# EasyEDA_ChisFlash_V1_0_Prometheus.net
KiCad netlist of a schematic drawn in EasyEDA Pro
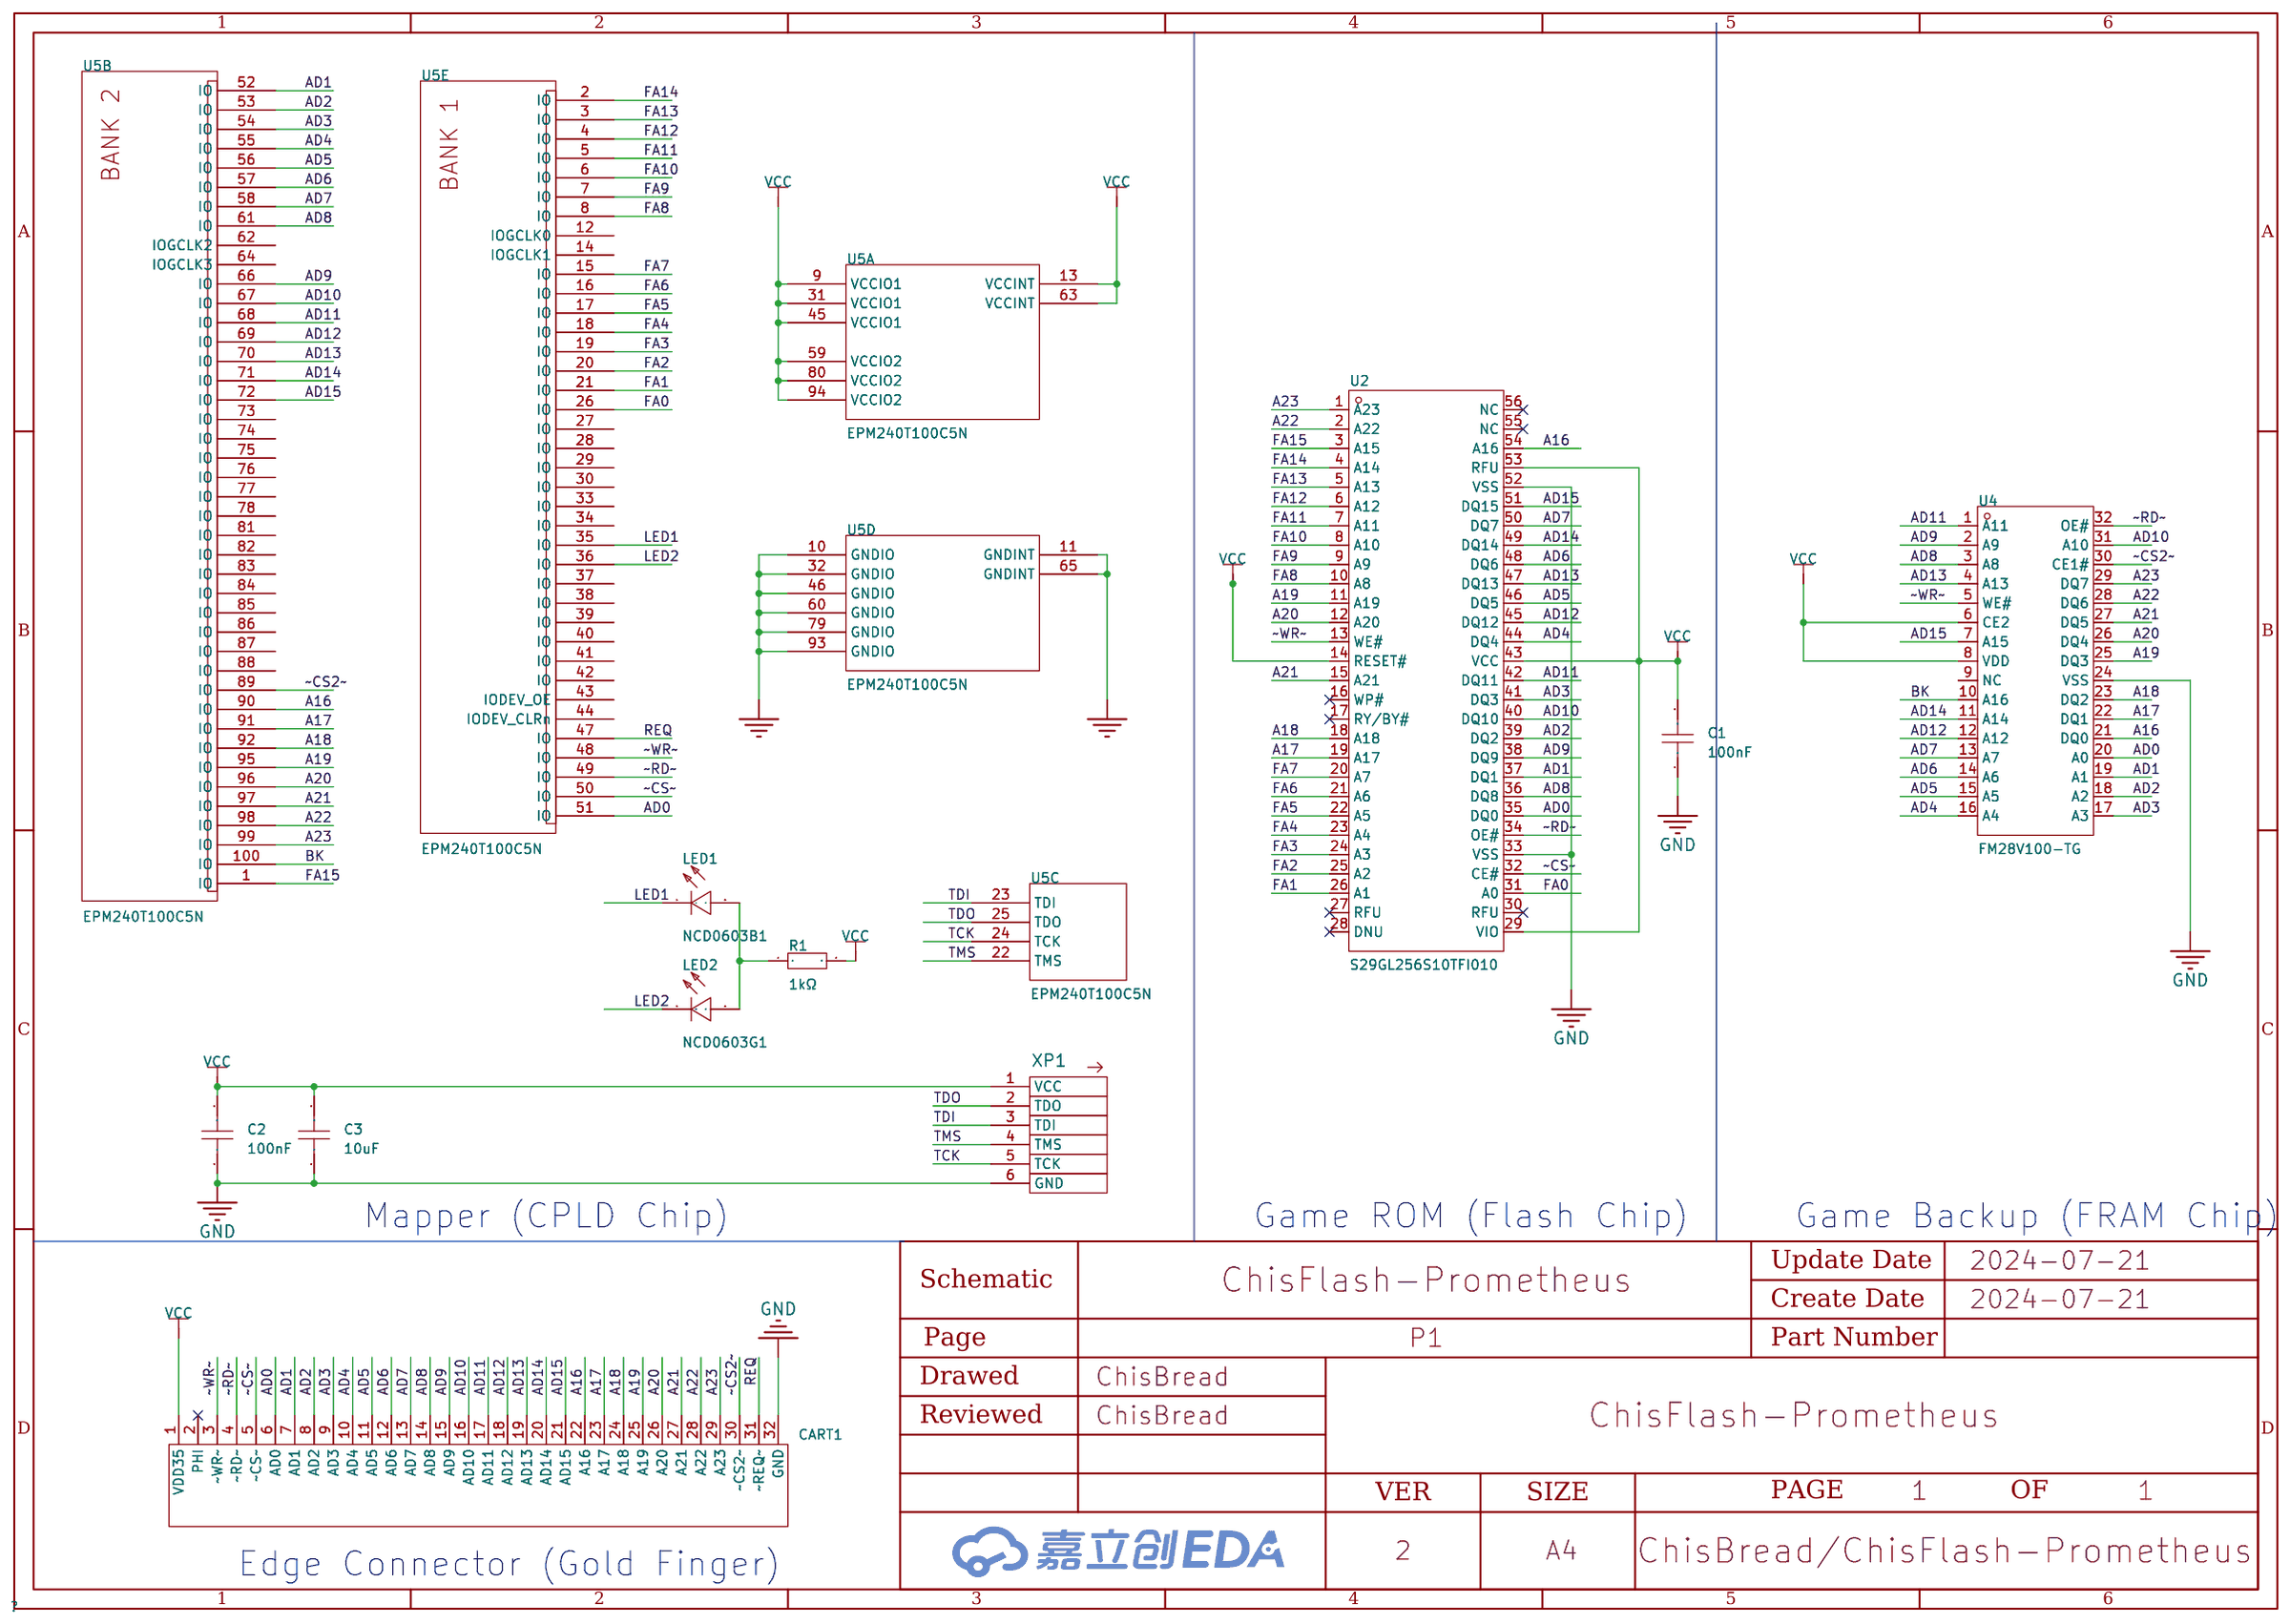
[diagram p0: schematic sheet]

(export (version "E")
  (design (tool "Eeschema 10.0.6"))
  (components
    (comp (ref "C1")
      (value "100nF")
      (footprint "easyedapro:C0603")
      (libsource (lib "easyedapro") (part "CapAcitance"))
    )
    (comp (ref "C2")
      (value "100nF")
      (footprint "easyedapro:C0603")
      (libsource (lib "easyedapro") (part "CapAcitance"))
    )
    (comp (ref "C3")
      (value "10uF")
      (footprint "easyedapro:C0603")
      (description "容值:10uF;精度:±20%;额定电压:25V;材质(温度系数):X5R;")
      (fields
        (field (name "Manufacturer Part") "CL10A106MA8NRNC")
        (field (name "Manufacturer") "SAMSUNG(三星)")
      )
      (libsource (lib "easyedapro") (part "CL10A106MA8NRNC"))
    )
    (comp (ref "CART1")
      (value "~")
      (footprint "easyedapro:GBACartridge")
      (description "GBA Cartridge")
      (libsource (lib "easyedapro") (part "GBACartridge"))
    )
    (comp (ref "LED1")
      (value "NCD0603B1")
      (footprint "easyedapro:LED0603-RD")
      (fields (field (name "Manufacturer") "国星光电"))
      (libsource (lib "easyedapro") (part "FC-DA1608BK-470H10"))
    )
    (comp (ref "LED2")
      (value "NCD0603G1")
      (footprint "easyedapro:LED0603-RD")
      (fields (field (name "Manufacturer") "国星光电"))
      (libsource (lib "easyedapro") (part "FC-D1608UGK-520D10"))
    )
    (comp (ref "R1")
      (value "1kΩ")
      (footprint "easyedapro:R0603")
      (description "电阻类型:厚膜电阻;阻值:1kΩ;精度:±1%;功率:100mW;最大工作电压:75V;温度系数:±100ppm/°C;")
      (fields
        (field (name "Manufacturer Part") "0603WAF1001T5E")
        (field (name "Manufacturer") "UNI-ROYAL(厚声)")
      )
      (libsource (lib "easyedapro") (part "0603WAF1001T5E"))
    )
    (comp (ref "U2")
      (value "S29GL256S10TFI010")
      (footprint "easyedapro:TSOP-56_L18.4-W14.0-P0.50-LS20.0-TL")
      (fields (field (name "Manufacturer") "SPANSION(飞索)"))
      (libsource (lib "easyedapro") (part "S29GL256S10TFI010"))
    )
    (comp (ref "U4")
      (value "FM28V100-TG")
      (fields (field (name "Manufacturer") "CYPRESS(赛普拉斯)"))
      (libsource (lib "easyedapro") (part "FM28V100-TG_C2959453"))
    )
    (comp (ref "U5")
      (value "EPM240T100C5N")
      (footprint "easyedapro:TQFP-100_L14.0-W14.0-P0.50-LS16.0-BL")
      (description "类型:其它PLD;逻辑门数量:-;逻辑单元数:-;逻辑阵列块数:240;")
      (fields (field (name "Manufacturer") "Intel/Altera"))
      (libsource (lib "easyedapro") (part "EPM240T100C5N"))
    )
    (comp (ref "XP1")
      (value "JTAG")
      (footprint "easyedapro:HDR-TH_6P-P1.27-V-M-1")
      (libsource (lib "easyedapro") (part "jtag"))
    )
  )
  (nets
    (net (code "1") (name "/A16") (class "Default")
      (node (ref "CART1") (pin "22") (pinfunction "A16_22") (pintype "input"))
      (node (ref "U2") (pin "54") (pinfunction "A16_54") (pintype "input"))
      (node (ref "U4") (pin "21") (pinfunction "DQ0_21") (pintype "unspecified"))
      (node (ref "U5") (pin "90") (pinfunction "IO_90") (pintype "bidirectional"))
    )
    (net (code "2") (name "/A17") (class "Default")
      (node (ref "CART1") (pin "23") (pinfunction "A17_23") (pintype "input"))
      (node (ref "U2") (pin "19") (pinfunction "A17_19") (pintype "input"))
      (node (ref "U4") (pin "22") (pinfunction "DQ1_22") (pintype "unspecified"))
      (node (ref "U5") (pin "91") (pinfunction "IO_91") (pintype "bidirectional"))
    )
    (net (code "3") (name "/A18") (class "Default")
      (node (ref "CART1") (pin "24") (pinfunction "A18_24") (pintype "input"))
      (node (ref "U2") (pin "18") (pinfunction "A18_18") (pintype "input"))
      (node (ref "U4") (pin "23") (pinfunction "DQ2_23") (pintype "unspecified"))
      (node (ref "U5") (pin "92") (pinfunction "IO_92") (pintype "bidirectional"))
    )
    (net (code "4") (name "/A19") (class "Default")
      (node (ref "CART1") (pin "25") (pinfunction "A19_25") (pintype "input"))
      (node (ref "U2") (pin "11") (pinfunction "A19_11") (pintype "input"))
      (node (ref "U4") (pin "25") (pinfunction "DQ3_25") (pintype "unspecified"))
      (node (ref "U5") (pin "95") (pinfunction "IO_95") (pintype "bidirectional"))
    )
    (net (code "5") (name "/A20") (class "Default")
      (node (ref "CART1") (pin "26") (pinfunction "A20_26") (pintype "input"))
      (node (ref "U2") (pin "12") (pinfunction "A20_12") (pintype "input"))
      (node (ref "U4") (pin "26") (pinfunction "DQ4_26") (pintype "unspecified"))
      (node (ref "U5") (pin "96") (pinfunction "IO_96") (pintype "bidirectional"))
    )
    (net (code "6") (name "/A21") (class "Default")
      (node (ref "CART1") (pin "27") (pinfunction "A21_27") (pintype "input"))
      (node (ref "U2") (pin "15") (pinfunction "A21_15") (pintype "input"))
      (node (ref "U4") (pin "27") (pinfunction "DQ5_27") (pintype "unspecified"))
      (node (ref "U5") (pin "97") (pinfunction "IO_97") (pintype "bidirectional"))
    )
    (net (code "7") (name "/A22") (class "Default")
      (node (ref "CART1") (pin "28") (pinfunction "A22_28") (pintype "input"))
      (node (ref "U2") (pin "2") (pinfunction "A22_2") (pintype "input"))
      (node (ref "U4") (pin "28") (pinfunction "DQ6_28") (pintype "unspecified"))
      (node (ref "U5") (pin "98") (pinfunction "IO_98") (pintype "bidirectional"))
    )
    (net (code "8") (name "/A23") (class "Default")
      (node (ref "CART1") (pin "29") (pinfunction "A23_29") (pintype "input"))
      (node (ref "U2") (pin "1") (pinfunction "A23_1") (pintype "input"))
      (node (ref "U4") (pin "29") (pinfunction "DQ7_29") (pintype "unspecified"))
      (node (ref "U5") (pin "99") (pinfunction "IO_99") (pintype "bidirectional"))
    )
    (net (code "9") (name "/AD0") (class "Default")
      (node (ref "CART1") (pin "6") (pinfunction "AD0_6") (pintype "input"))
      (node (ref "U2") (pin "35") (pinfunction "DQ0_35") (pintype "input"))
      (node (ref "U4") (pin "20") (pinfunction "A0_20") (pintype "unspecified"))
      (node (ref "U5") (pin "51") (pinfunction "IO_51") (pintype "bidirectional"))
    )
    (net (code "10") (name "/AD1") (class "Default")
      (node (ref "CART1") (pin "7") (pinfunction "AD1_7") (pintype "input"))
      (node (ref "U2") (pin "37") (pinfunction "DQ1_37") (pintype "input"))
      (node (ref "U4") (pin "19") (pinfunction "A1_19") (pintype "unspecified"))
      (node (ref "U5") (pin "52") (pinfunction "IO_52") (pintype "bidirectional"))
    )
    (net (code "11") (name "/AD2") (class "Default")
      (node (ref "CART1") (pin "8") (pinfunction "AD2_8") (pintype "input"))
      (node (ref "U2") (pin "39") (pinfunction "DQ2_39") (pintype "input"))
      (node (ref "U4") (pin "18") (pinfunction "A2_18") (pintype "unspecified"))
      (node (ref "U5") (pin "53") (pinfunction "IO_53") (pintype "bidirectional"))
    )
    (net (code "12") (name "/AD3") (class "Default")
      (node (ref "CART1") (pin "9") (pinfunction "AD3_9") (pintype "input"))
      (node (ref "U2") (pin "41") (pinfunction "DQ3_41") (pintype "input"))
      (node (ref "U4") (pin "17") (pinfunction "A3_17") (pintype "unspecified"))
      (node (ref "U5") (pin "54") (pinfunction "IO_54") (pintype "bidirectional"))
    )
    (net (code "13") (name "/AD4") (class "Default")
      (node (ref "CART1") (pin "10") (pinfunction "AD4_10") (pintype "input"))
      (node (ref "U2") (pin "44") (pinfunction "DQ4_44") (pintype "input"))
      (node (ref "U4") (pin "16") (pinfunction "A4_16") (pintype "unspecified"))
      (node (ref "U5") (pin "55") (pinfunction "IO_55") (pintype "bidirectional"))
    )
    (net (code "14") (name "/AD5") (class "Default")
      (node (ref "CART1") (pin "11") (pinfunction "AD5_11") (pintype "input"))
      (node (ref "U2") (pin "46") (pinfunction "DQ5_46") (pintype "input"))
      (node (ref "U4") (pin "15") (pinfunction "A5_15") (pintype "unspecified"))
      (node (ref "U5") (pin "56") (pinfunction "IO_56") (pintype "bidirectional"))
    )
    (net (code "15") (name "/AD6") (class "Default")
      (node (ref "CART1") (pin "12") (pinfunction "AD6_12") (pintype "input"))
      (node (ref "U2") (pin "48") (pinfunction "DQ6_48") (pintype "input"))
      (node (ref "U4") (pin "14") (pinfunction "A6_14") (pintype "unspecified"))
      (node (ref "U5") (pin "57") (pinfunction "IO_57") (pintype "bidirectional"))
    )
    (net (code "16") (name "/AD7") (class "Default")
      (node (ref "CART1") (pin "13") (pinfunction "AD7_13") (pintype "input"))
      (node (ref "U2") (pin "50") (pinfunction "DQ7_50") (pintype "input"))
      (node (ref "U4") (pin "13") (pinfunction "A7_13") (pintype "unspecified"))
      (node (ref "U5") (pin "58") (pinfunction "IO_58") (pintype "bidirectional"))
    )
    (net (code "17") (name "/AD8") (class "Default")
      (node (ref "CART1") (pin "14") (pinfunction "AD8_14") (pintype "input"))
      (node (ref "U2") (pin "36") (pinfunction "DQ8_36") (pintype "input"))
      (node (ref "U4") (pin "3") (pinfunction "A8_3") (pintype "unspecified"))
      (node (ref "U5") (pin "61") (pinfunction "IO_61") (pintype "bidirectional"))
    )
    (net (code "18") (name "/AD9") (class "Default")
      (node (ref "CART1") (pin "15") (pinfunction "AD9_15") (pintype "input"))
      (node (ref "U2") (pin "38") (pinfunction "DQ9_38") (pintype "input"))
      (node (ref "U4") (pin "2") (pinfunction "A9_2") (pintype "unspecified"))
      (node (ref "U5") (pin "66") (pinfunction "IO_66") (pintype "bidirectional"))
    )
    (net (code "19") (name "/AD10") (class "Default")
      (node (ref "CART1") (pin "16") (pinfunction "AD10_16") (pintype "input"))
      (node (ref "U2") (pin "40") (pinfunction "DQ10_40") (pintype "input"))
      (node (ref "U4") (pin "31") (pinfunction "A10_31") (pintype "unspecified"))
      (node (ref "U5") (pin "67") (pinfunction "IO_67") (pintype "bidirectional"))
    )
    (net (code "20") (name "/AD11") (class "Default")
      (node (ref "CART1") (pin "17") (pinfunction "AD11_17") (pintype "input"))
      (node (ref "U2") (pin "42") (pinfunction "DQ11_42") (pintype "input"))
      (node (ref "U4") (pin "1") (pinfunction "A11_1") (pintype "unspecified"))
      (node (ref "U5") (pin "68") (pinfunction "IO_68") (pintype "bidirectional"))
    )
    (net (code "21") (name "/AD12") (class "Default")
      (node (ref "CART1") (pin "18") (pinfunction "AD12_18") (pintype "input"))
      (node (ref "U2") (pin "45") (pinfunction "DQ12_45") (pintype "input"))
      (node (ref "U4") (pin "12") (pinfunction "A12_12") (pintype "unspecified"))
      (node (ref "U5") (pin "69") (pinfunction "IO_69") (pintype "bidirectional"))
    )
    (net (code "22") (name "/AD13") (class "Default")
      (node (ref "CART1") (pin "19") (pinfunction "AD13_19") (pintype "input"))
      (node (ref "U2") (pin "47") (pinfunction "DQ13_47") (pintype "input"))
      (node (ref "U4") (pin "4") (pinfunction "A13_4") (pintype "unspecified"))
      (node (ref "U5") (pin "70") (pinfunction "IO_70") (pintype "bidirectional"))
    )
    (net (code "23") (name "/AD14") (class "Default")
      (node (ref "CART1") (pin "20") (pinfunction "AD14_20") (pintype "input"))
      (node (ref "U2") (pin "49") (pinfunction "DQ14_49") (pintype "input"))
      (node (ref "U4") (pin "11") (pinfunction "A14_11") (pintype "unspecified"))
      (node (ref "U5") (pin "71") (pinfunction "IO_71") (pintype "bidirectional"))
    )
    (net (code "24") (name "/AD15") (class "Default")
      (node (ref "CART1") (pin "21") (pinfunction "AD15_21") (pintype "input"))
      (node (ref "U2") (pin "51") (pinfunction "DQ15_51") (pintype "input"))
      (node (ref "U4") (pin "7") (pinfunction "A15_7") (pintype "unspecified"))
      (node (ref "U5") (pin "72") (pinfunction "IO_72") (pintype "bidirectional"))
    )
    (net (code "25") (name "/BK") (class "Default")
      (node (ref "U4") (pin "10") (pinfunction "A16_10") (pintype "unspecified"))
      (node (ref "U5") (pin "100") (pinfunction "IO_100") (pintype "bidirectional"))
    )
    (net (code "26") (name "/FA0") (class "Default")
      (node (ref "U2") (pin "31") (pinfunction "A0_31") (pintype "input"))
      (node (ref "U5") (pin "26") (pinfunction "IO_26") (pintype "bidirectional"))
    )
    (net (code "27") (name "/FA1") (class "Default")
      (node (ref "U2") (pin "26") (pinfunction "A1_26") (pintype "input"))
      (node (ref "U5") (pin "21") (pinfunction "IO_21") (pintype "bidirectional"))
    )
    (net (code "28") (name "/FA2") (class "Default")
      (node (ref "U2") (pin "25") (pinfunction "A2_25") (pintype "input"))
      (node (ref "U5") (pin "20") (pinfunction "IO_20") (pintype "bidirectional"))
    )
    (net (code "29") (name "/FA3") (class "Default")
      (node (ref "U2") (pin "24") (pinfunction "A3_24") (pintype "input"))
      (node (ref "U5") (pin "19") (pinfunction "IO_19") (pintype "bidirectional"))
    )
    (net (code "30") (name "/FA4") (class "Default")
      (node (ref "U2") (pin "23") (pinfunction "A4_23") (pintype "input"))
      (node (ref "U5") (pin "18") (pinfunction "IO_18") (pintype "bidirectional"))
    )
    (net (code "31") (name "/FA5") (class "Default")
      (node (ref "U2") (pin "22") (pinfunction "A5_22") (pintype "input"))
      (node (ref "U5") (pin "17") (pinfunction "IO_17") (pintype "bidirectional"))
    )
    (net (code "32") (name "/FA6") (class "Default")
      (node (ref "U2") (pin "21") (pinfunction "A6_21") (pintype "input"))
      (node (ref "U5") (pin "16") (pinfunction "IO_16") (pintype "bidirectional"))
    )
    (net (code "33") (name "/FA7") (class "Default")
      (node (ref "U2") (pin "20") (pinfunction "A7_20") (pintype "input"))
      (node (ref "U5") (pin "15") (pinfunction "IO_15") (pintype "bidirectional"))
    )
    (net (code "34") (name "/FA8") (class "Default")
      (node (ref "U2") (pin "10") (pinfunction "A8_10") (pintype "input"))
      (node (ref "U5") (pin "8") (pinfunction "IO_8") (pintype "bidirectional"))
    )
    (net (code "35") (name "/FA9") (class "Default")
      (node (ref "U2") (pin "9") (pinfunction "A9_9") (pintype "input"))
      (node (ref "U5") (pin "7") (pinfunction "IO_7") (pintype "bidirectional"))
    )
    (net (code "36") (name "/FA10") (class "Default")
      (node (ref "U2") (pin "8") (pinfunction "A10_8") (pintype "input"))
      (node (ref "U5") (pin "6") (pinfunction "IO_6") (pintype "bidirectional"))
    )
    (net (code "37") (name "/FA11") (class "Default")
      (node (ref "U2") (pin "7") (pinfunction "A11_7") (pintype "input"))
      (node (ref "U5") (pin "5") (pinfunction "IO_5") (pintype "bidirectional"))
    )
    (net (code "38") (name "/FA12") (class "Default")
      (node (ref "U2") (pin "6") (pinfunction "A12_6") (pintype "input"))
      (node (ref "U5") (pin "4") (pinfunction "IO_4") (pintype "bidirectional"))
    )
    (net (code "39") (name "/FA13") (class "Default")
      (node (ref "U2") (pin "5") (pinfunction "A13_5") (pintype "input"))
      (node (ref "U5") (pin "3") (pinfunction "IO_3") (pintype "bidirectional"))
    )
    (net (code "40") (name "/FA14") (class "Default")
      (node (ref "U2") (pin "4") (pinfunction "A14_4") (pintype "input"))
      (node (ref "U5") (pin "2") (pinfunction "IO_2") (pintype "bidirectional"))
    )
    (net (code "41") (name "/FA15") (class "Default")
      (node (ref "U2") (pin "3") (pinfunction "A15_3") (pintype "input"))
      (node (ref "U5") (pin "1") (pinfunction "IO_1") (pintype "bidirectional"))
    )
    (net (code "42") (name "/LED1") (class "Default")
      (node (ref "LED1") (pin "1") (pinfunction "-_1") (pintype "input"))
      (node (ref "U5") (pin "35") (pinfunction "IO_35") (pintype "bidirectional"))
    )
    (net (code "43") (name "/LED2") (class "Default")
      (node (ref "LED2") (pin "1") (pinfunction "K_1") (pintype "input"))
      (node (ref "U5") (pin "36") (pinfunction "IO_36") (pintype "bidirectional"))
    )
    (net (code "44") (name "/REQ") (class "Default")
      (node (ref "CART1") (pin "31") (pinfunction "~REQ~_31") (pintype "input"))
      (node (ref "U5") (pin "47") (pinfunction "IO_47") (pintype "bidirectional"))
    )
    (net (code "45") (name "/TCK") (class "Default")
      (node (ref "U5") (pin "24") (pinfunction "TCK_24") (pintype "unspecified"))
      (node (ref "XP1") (pin "5") (pinfunction "TCK_5") (pintype "input"))
    )
    (net (code "46") (name "/TDI") (class "Default")
      (node (ref "U5") (pin "23") (pinfunction "TDI_23") (pintype "unspecified"))
      (node (ref "XP1") (pin "3") (pinfunction "TDI_3") (pintype "output"))
    )
    (net (code "47") (name "/TDO") (class "Default")
      (node (ref "U5") (pin "25") (pinfunction "TDO_25") (pintype "output"))
      (node (ref "XP1") (pin "2") (pinfunction "TDO_2") (pintype "output"))
    )
    (net (code "48") (name "/TMS") (class "Default")
      (node (ref "U5") (pin "22") (pinfunction "TMS_22") (pintype "unspecified"))
      (node (ref "XP1") (pin "4") (pinfunction "TMS_4") (pintype "output"))
    )
    (net (code "49") (name "/~CS2~") (class "Default")
      (node (ref "CART1") (pin "30") (pinfunction "~CS2~_30") (pintype "input"))
      (node (ref "U4") (pin "30") (pinfunction "CE1#_30") (pintype "unspecified"))
      (node (ref "U5") (pin "89") (pinfunction "IO_89") (pintype "bidirectional"))
    )
    (net (code "50") (name "/~CS~") (class "Default")
      (node (ref "CART1") (pin "5") (pinfunction "~CS~_5") (pintype "input"))
      (node (ref "U2") (pin "32") (pinfunction "CE#_32") (pintype "input"))
      (node (ref "U5") (pin "50") (pinfunction "IO_50") (pintype "bidirectional"))
    )
    (net (code "51") (name "/~RD~") (class "Default")
      (node (ref "CART1") (pin "4") (pinfunction "~RD~_4") (pintype "input"))
      (node (ref "U2") (pin "34") (pinfunction "OE#_34") (pintype "input"))
      (node (ref "U4") (pin "32") (pinfunction "OE#_32") (pintype "unspecified"))
      (node (ref "U5") (pin "49") (pinfunction "IO_49") (pintype "bidirectional"))
    )
    (net (code "52") (name "/~WR~") (class "Default")
      (node (ref "CART1") (pin "3") (pinfunction "~WR~_3") (pintype "input"))
      (node (ref "U2") (pin "13") (pinfunction "WE#_13") (pintype "input"))
      (node (ref "U4") (pin "5") (pinfunction "WE#_5") (pintype "unspecified"))
      (node (ref "U5") (pin "48") (pinfunction "IO_48") (pintype "bidirectional"))
    )
    (net (code "53") (name "GND") (class "Default")
      (node (ref "C1") (pin "1") (pinfunction "1_1") (pintype "input"))
      (node (ref "C2") (pin "1") (pinfunction "1_1") (pintype "input"))
      (node (ref "C3") (pin "1") (pinfunction "1_1") (pintype "unspecified"))
      (node (ref "CART1") (pin "32") (pinfunction "GND_32") (pintype "input"))
      (node (ref "U2") (pin "33") (pinfunction "VSS_33") (pintype "input"))
      (node (ref "U2") (pin "52") (pinfunction "VSS_52") (pintype "input"))
      (node (ref "U4") (pin "24") (pinfunction "VSS_24") (pintype "unspecified"))
      (node (ref "U5") (pin "10") (pinfunction "GNDIO_10") (pintype "unspecified"))
      (node (ref "U5") (pin "11") (pinfunction "GNDINT_11") (pintype "unspecified"))
      (node (ref "U5") (pin "32") (pinfunction "GNDIO_32") (pintype "unspecified"))
      (node (ref "U5") (pin "46") (pinfunction "GNDIO_46") (pintype "unspecified"))
      (node (ref "U5") (pin "60") (pinfunction "GNDIO_60") (pintype "unspecified"))
      (node (ref "U5") (pin "65") (pinfunction "GNDINT_65") (pintype "unspecified"))
      (node (ref "U5") (pin "79") (pinfunction "GNDIO_79") (pintype "unspecified"))
      (node (ref "U5") (pin "93") (pinfunction "GNDIO_93") (pintype "unspecified"))
      (node (ref "XP1") (pin "6") (pinfunction "GND_6") (pintype "input"))
    )
    (net (code "54") (name "Net-(LED1-+)") (class "Default")
      (node (ref "LED1") (pin "2") (pinfunction "+_2") (pintype "input"))
      (node (ref "LED2") (pin "2") (pinfunction "A_2") (pintype "input"))
      (node (ref "R1") (pin "1") (pinfunction "1_1") (pintype "input"))
    )
    (net (code "55") (name "VCC") (class "Default")
      (node (ref "C1") (pin "2") (pinfunction "2_2") (pintype "input"))
      (node (ref "C2") (pin "2") (pinfunction "2_2") (pintype "input"))
      (node (ref "C3") (pin "2") (pinfunction "2_2") (pintype "unspecified"))
      (node (ref "CART1") (pin "1") (pinfunction "VDD35_1") (pintype "input"))
      (node (ref "R1") (pin "2") (pinfunction "2_2") (pintype "input"))
      (node (ref "U2") (pin "14") (pinfunction "RESET#_14") (pintype "input"))
      (node (ref "U2") (pin "29") (pinfunction "VIO_29") (pintype "input"))
      (node (ref "U2") (pin "43") (pinfunction "VCC_43") (pintype "input"))
      (node (ref "U2") (pin "53") (pinfunction "RFU_53") (pintype "input"))
      (node (ref "U4") (pin "6") (pinfunction "CE2_6") (pintype "unspecified"))
      (node (ref "U4") (pin "8") (pinfunction "VDD_8") (pintype "unspecified"))
      (node (ref "U5") (pin "13") (pinfunction "VCCINT_13") (pintype "unspecified"))
      (node (ref "U5") (pin "31") (pinfunction "VCCIO1_31") (pintype "unspecified"))
      (node (ref "U5") (pin "45") (pinfunction "VCCIO1_45") (pintype "unspecified"))
      (node (ref "U5") (pin "59") (pinfunction "VCCIO2_59") (pintype "unspecified"))
      (node (ref "U5") (pin "63") (pinfunction "VCCINT_63") (pintype "unspecified"))
      (node (ref "U5") (pin "80") (pinfunction "VCCIO2_80") (pintype "unspecified"))
      (node (ref "U5") (pin "9") (pinfunction "VCCIO1_9") (pintype "unspecified"))
      (node (ref "U5") (pin "94") (pinfunction "VCCIO2_94") (pintype "unspecified"))
      (node (ref "XP1") (pin "1") (pinfunction "VCC_1") (pintype "output"))
    )
    (net (code "56") (name "unconnected-(CART1-PHI-Pad2)") (class "Default")
      (node (ref "CART1") (pin "2") (pinfunction "PHI_2") (pintype "input+no_connect"))
    )
    (net (code "57") (name "unconnected-(U2-DNU-Pad28)") (class "Default")
      (node (ref "U2") (pin "28") (pinfunction "DNU_28") (pintype "input+no_connect"))
    )
    (net (code "58") (name "unconnected-(U2-NC-Pad55)") (class "Default")
      (node (ref "U2") (pin "55") (pinfunction "NC_55") (pintype "input+no_connect"))
    )
    (net (code "59") (name "unconnected-(U2-NC-Pad56)") (class "Default")
      (node (ref "U2") (pin "56") (pinfunction "NC_56") (pintype "input+no_connect"))
    )
    (net (code "60") (name "unconnected-(U2-RFU-Pad27)") (class "Default")
      (node (ref "U2") (pin "27") (pinfunction "RFU_27") (pintype "input+no_connect"))
    )
    (net (code "61") (name "unconnected-(U2-RFU-Pad30)") (class "Default")
      (node (ref "U2") (pin "30") (pinfunction "RFU_30") (pintype "input+no_connect"))
    )
    (net (code "62") (name "unconnected-(U2-RY{slash}BY#-Pad17)") (class "Default")
      (node (ref "U2") (pin "17") (pinfunction "RY/BY#_17") (pintype "input+no_connect"))
    )
    (net (code "63") (name "unconnected-(U2-WP#-Pad16)") (class "Default")
      (node (ref "U2") (pin "16") (pinfunction "WP#_16") (pintype "input+no_connect"))
    )
    (net (code "64") (name "unconnected-(U4-NC-Pad9)") (class "Default")
      (node (ref "U4") (pin "9") (pinfunction "NC_9") (pintype "unspecified"))
    )
    (net (code "65") (name "unconnected-(U5B-IO-Pad73)") (class "Default")
      (node (ref "U5") (pin "73") (pinfunction "IO_73") (pintype "bidirectional"))
    )
    (net (code "66") (name "unconnected-(U5B-IO-Pad74)") (class "Default")
      (node (ref "U5") (pin "74") (pinfunction "IO_74") (pintype "bidirectional"))
    )
    (net (code "67") (name "unconnected-(U5B-IO-Pad75)") (class "Default")
      (node (ref "U5") (pin "75") (pinfunction "IO_75") (pintype "bidirectional"))
    )
    (net (code "68") (name "unconnected-(U5B-IO-Pad76)") (class "Default")
      (node (ref "U5") (pin "76") (pinfunction "IO_76") (pintype "bidirectional"))
    )
    (net (code "69") (name "unconnected-(U5B-IO-Pad77)") (class "Default")
      (node (ref "U5") (pin "77") (pinfunction "IO_77") (pintype "bidirectional"))
    )
    (net (code "70") (name "unconnected-(U5B-IO-Pad78)") (class "Default")
      (node (ref "U5") (pin "78") (pinfunction "IO_78") (pintype "bidirectional"))
    )
    (net (code "71") (name "unconnected-(U5B-IO-Pad81)") (class "Default")
      (node (ref "U5") (pin "81") (pinfunction "IO_81") (pintype "bidirectional"))
    )
    (net (code "72") (name "unconnected-(U5B-IO-Pad82)") (class "Default")
      (node (ref "U5") (pin "82") (pinfunction "IO_82") (pintype "bidirectional"))
    )
    (net (code "73") (name "unconnected-(U5B-IO-Pad83)") (class "Default")
      (node (ref "U5") (pin "83") (pinfunction "IO_83") (pintype "bidirectional"))
    )
    (net (code "74") (name "unconnected-(U5B-IO-Pad84)") (class "Default")
      (node (ref "U5") (pin "84") (pinfunction "IO_84") (pintype "bidirectional"))
    )
    (net (code "75") (name "unconnected-(U5B-IO-Pad85)") (class "Default")
      (node (ref "U5") (pin "85") (pinfunction "IO_85") (pintype "bidirectional"))
    )
    (net (code "76") (name "unconnected-(U5B-IO-Pad86)") (class "Default")
      (node (ref "U5") (pin "86") (pinfunction "IO_86") (pintype "bidirectional"))
    )
    (net (code "77") (name "unconnected-(U5B-IO-Pad87)") (class "Default")
      (node (ref "U5") (pin "87") (pinfunction "IO_87") (pintype "bidirectional"))
    )
    (net (code "78") (name "unconnected-(U5B-IO-Pad88)") (class "Default")
      (node (ref "U5") (pin "88") (pinfunction "IO_88") (pintype "bidirectional"))
    )
    (net (code "79") (name "unconnected-(U5B-IOGCLK2-Pad62)") (class "Default")
      (node (ref "U5") (pin "62") (pinfunction "IOGCLK2_62") (pintype "bidirectional"))
    )
    (net (code "80") (name "unconnected-(U5B-IOGCLK3-Pad64)") (class "Default")
      (node (ref "U5") (pin "64") (pinfunction "IOGCLK3_64") (pintype "bidirectional"))
    )
    (net (code "81") (name "unconnected-(U5E-IO-Pad27)") (class "Default")
      (node (ref "U5") (pin "27") (pinfunction "IO_27") (pintype "bidirectional"))
    )
    (net (code "82") (name "unconnected-(U5E-IO-Pad28)") (class "Default")
      (node (ref "U5") (pin "28") (pinfunction "IO_28") (pintype "bidirectional"))
    )
    (net (code "83") (name "unconnected-(U5E-IO-Pad29)") (class "Default")
      (node (ref "U5") (pin "29") (pinfunction "IO_29") (pintype "bidirectional"))
    )
    (net (code "84") (name "unconnected-(U5E-IO-Pad30)") (class "Default")
      (node (ref "U5") (pin "30") (pinfunction "IO_30") (pintype "bidirectional"))
    )
    (net (code "85") (name "unconnected-(U5E-IO-Pad33)") (class "Default")
      (node (ref "U5") (pin "33") (pinfunction "IO_33") (pintype "bidirectional"))
    )
    (net (code "86") (name "unconnected-(U5E-IO-Pad34)") (class "Default")
      (node (ref "U5") (pin "34") (pinfunction "IO_34") (pintype "bidirectional"))
    )
    (net (code "87") (name "unconnected-(U5E-IO-Pad37)") (class "Default")
      (node (ref "U5") (pin "37") (pinfunction "IO_37") (pintype "bidirectional"))
    )
    (net (code "88") (name "unconnected-(U5E-IO-Pad38)") (class "Default")
      (node (ref "U5") (pin "38") (pinfunction "IO_38") (pintype "bidirectional"))
    )
    (net (code "89") (name "unconnected-(U5E-IO-Pad39)") (class "Default")
      (node (ref "U5") (pin "39") (pinfunction "IO_39") (pintype "bidirectional"))
    )
    (net (code "90") (name "unconnected-(U5E-IO-Pad40)") (class "Default")
      (node (ref "U5") (pin "40") (pinfunction "IO_40") (pintype "bidirectional"))
    )
    (net (code "91") (name "unconnected-(U5E-IO-Pad41)") (class "Default")
      (node (ref "U5") (pin "41") (pinfunction "IO_41") (pintype "bidirectional"))
    )
    (net (code "92") (name "unconnected-(U5E-IO-Pad42)") (class "Default")
      (node (ref "U5") (pin "42") (pinfunction "IO_42") (pintype "bidirectional"))
    )
    (net (code "93") (name "unconnected-(U5E-IODEV_CLRn-Pad44)") (class "Default")
      (node (ref "U5") (pin "44") (pinfunction "IODEV_CLRn_44") (pintype "bidirectional"))
    )
    (net (code "94") (name "unconnected-(U5E-IODEV_OE-Pad43)") (class "Default")
      (node (ref "U5") (pin "43") (pinfunction "IODEV_OE_43") (pintype "bidirectional"))
    )
    (net (code "95") (name "unconnected-(U5E-IOGCLK0-Pad12)") (class "Default")
      (node (ref "U5") (pin "12") (pinfunction "IOGCLK0_12") (pintype "bidirectional"))
    )
    (net (code "96") (name "unconnected-(U5E-IOGCLK1-Pad14)") (class "Default")
      (node (ref "U5") (pin "14") (pinfunction "IOGCLK1_14") (pintype "bidirectional"))
    )
  )
)
